# Schematic.net
KiCad netlist of a schematic drawn in EAGLE
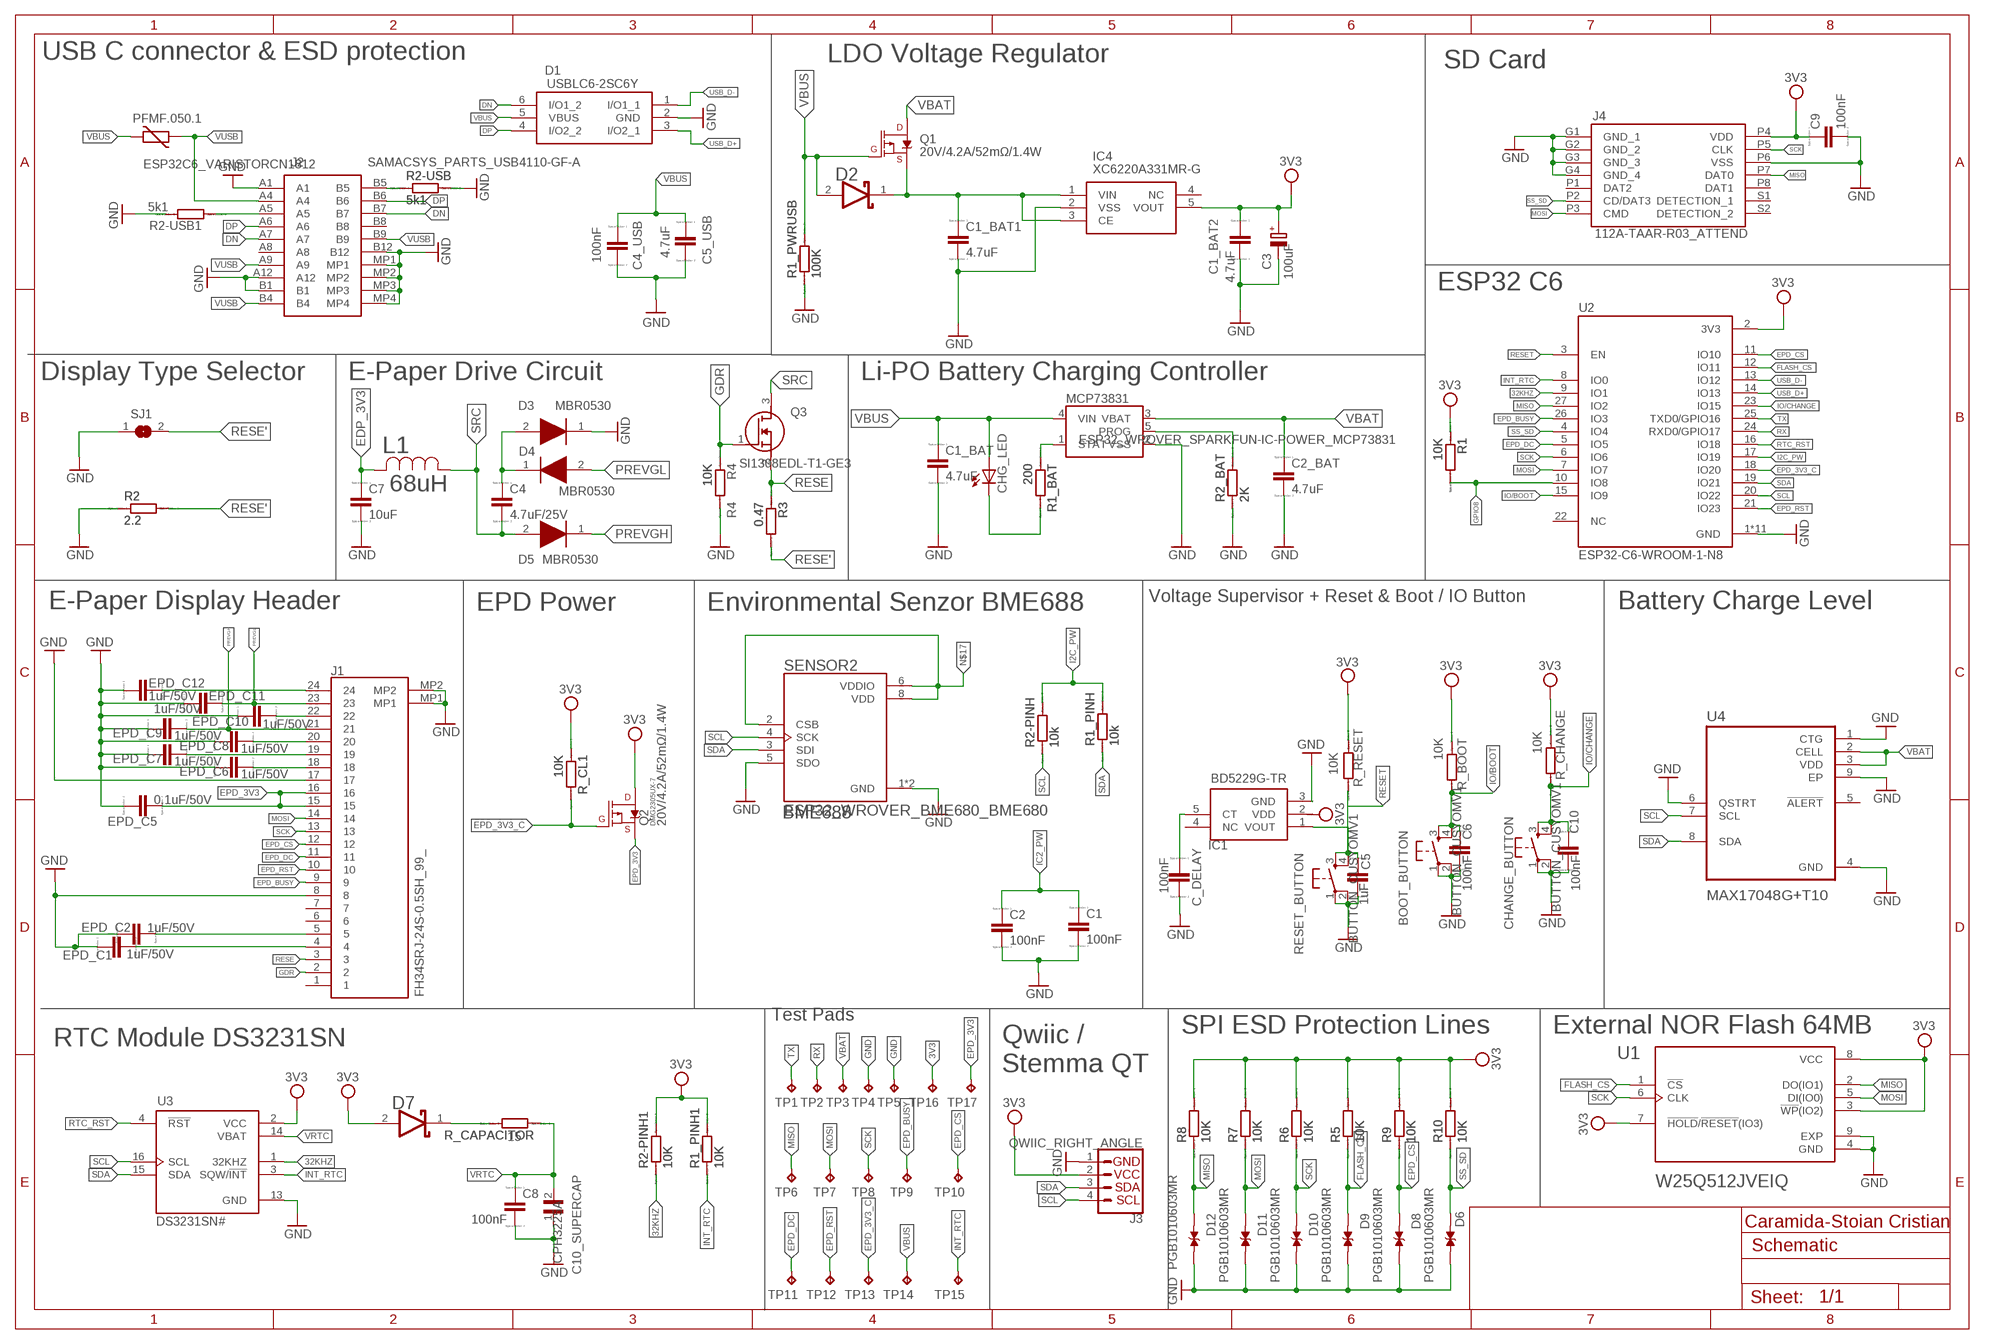
[diagram p0: schematic, sheet 1]

(export (version "E")
  (design (tool "Eeschema 10.0.6"))
  (components
    (comp (ref "BOOT_BUTTON")
      (value "BUTTON_CUSYOMV1")
      (footprint "eagle-import:MYBUTTON")
      (libsource (lib "eagle-import") (part "BUTTON_CUSYOMV1"))
    )
    (comp (ref "C1")
      (value "100nF")
      (footprint "eagle-import:ESP32_WROVER_EAGLE-LTSPICE_C0402")
      (libsource (lib "eagle-import") (part "ESP32_WROVER_EAGLE-LTSPICE_CC0402"))
    )
    (comp (ref "C1_BAT")
      (value "4.7uF")
      (footprint "eagle-import:ESP32_WROVER_EAGLE-LTSPICE_C0402")
      (libsource (lib "eagle-import") (part "ESP32_WROVER_EAGLE-LTSPICE_CC0402"))
    )
    (comp (ref "C1_BAT1")
      (value "4.7uF")
      (footprint "eagle-import:ESP32_WROVER_EAGLE-LTSPICE_C0402")
      (libsource (lib "eagle-import") (part "ESP32_WROVER_EAGLE-LTSPICE_CC0402"))
    )
    (comp (ref "C1_BAT2")
      (value "4.7uF")
      (footprint "eagle-import:ESP32_WROVER_EAGLE-LTSPICE_C0402")
      (libsource (lib "eagle-import") (part "ESP32_WROVER_EAGLE-LTSPICE_CC0402"))
    )
    (comp (ref "C2")
      (value "100nF")
      (footprint "eagle-import:ESP32_WROVER_EAGLE-LTSPICE_C0402")
      (libsource (lib "eagle-import") (part "ESP32_WROVER_EAGLE-LTSPICE_CC0402"))
    )
    (comp (ref "C2_BAT")
      (value "4.7uF")
      (footprint "eagle-import:ESP32_WROVER_EAGLE-LTSPICE_C0402")
      (libsource (lib "eagle-import") (part "ESP32_WROVER_EAGLE-LTSPICE_CC0402"))
    )
    (comp (ref "C3")
      (value "100uF")
      (footprint "eagle-import:RCL_CT3528")
      (libsource (lib "eagle-import") (part "RCL_CPOL-EUCT3528"))
    )
    (comp (ref "C4")
      (value "4.7uF/25V")
      (footprint "eagle-import:ESP32_WROVER_EAGLE-LTSPICE_C0402")
      (libsource (lib "eagle-import") (part "ESP32_WROVER_EAGLE-LTSPICE_CC0402"))
    )
    (comp (ref "C4_USB")
      (value "100nF")
      (footprint "eagle-import:ESP32_WROVER_EAGLE-LTSPICE_C0402")
      (libsource (lib "eagle-import") (part "ESP32_WROVER_EAGLE-LTSPICE_CC0402"))
    )
    (comp (ref "C5")
      (value "1uF")
      (footprint "eagle-import:ESP32_WROVER_EAGLE-LTSPICE_C0402")
      (libsource (lib "eagle-import") (part "EAGLE-LTSPICE_CC0402"))
    )
    (comp (ref "C5_USB")
      (value "4.7uF")
      (footprint "eagle-import:ESP32_WROVER_EAGLE-LTSPICE_C0402")
      (libsource (lib "eagle-import") (part "ESP32_WROVER_EAGLE-LTSPICE_CC0402"))
    )
    (comp (ref "C6")
      (value "100nF")
      (footprint "eagle-import:ESP32_WROVER_EAGLE-LTSPICE_C0402")
      (libsource (lib "eagle-import") (part "EAGLE-LTSPICE_CC0402"))
    )
    (comp (ref "C7")
      (value "10uF")
      (footprint "eagle-import:ESP32_WROVER_EAGLE-LTSPICE_C0402")
      (libsource (lib "eagle-import") (part "ESP32_WROVER_EAGLE-LTSPICE_CC0402"))
    )
    (comp (ref "C8")
      (value "100nF")
      (footprint "eagle-import:ESP32_WROVER_EAGLE-LTSPICE_C0402")
      (libsource (lib "eagle-import") (part "ESP32_WROVER_EAGLE-LTSPICE_CC0402"))
    )
    (comp (ref "C9")
      (value "100nF")
      (footprint "eagle-import:ESP32_WROVER_EAGLE-LTSPICE_C0402")
      (libsource (lib "eagle-import") (part "ESP32_WROVER_EAGLE-LTSPICE_CC0402"))
    )
    (comp (ref "C10")
      (value "100nF")
      (footprint "eagle-import:ESP32_WROVER_EAGLE-LTSPICE_C0402")
      (libsource (lib "eagle-import") (part "EAGLE-LTSPICE_CC0402"))
    )
    (comp (ref "C10_SUPERCAP")
      (value "CPH3225A")
      (footprint "eagle-import:CAPCP3225X100N")
      (fields (field (name "MF") "Seiko Instruments"))
      (libsource (lib "eagle-import") (part "CPH3225A"))
    )
    (comp (ref "CHANGE_BUTTON")
      (value "BUTTON_CUSYOMV1")
      (footprint "eagle-import:MYBUTTON")
      (libsource (lib "eagle-import") (part "BUTTON_CUSYOMV1"))
    )
    (comp (ref "CHG_LED")
      (value "ADAFRUIT_LEDCHIP-LED0603")
      (footprint "eagle-import:ADAFRUIT_CHIP-LED0603")
      (libsource (lib "eagle-import") (part "ADAFRUIT_LEDCHIP-LED0603"))
    )
    (comp (ref "C_DELAY")
      (value "100nF")
      (footprint "eagle-import:ESP32_WROVER_EAGLE-LTSPICE_C0402")
      (libsource (lib "eagle-import") (part "ESP32_WROVER_EAGLE-LTSPICE_CC0402"))
    )
    (comp (ref "D1")
      (value "USBLC6-2SC6Y")
      (footprint "eagle-import:SOT95P280X145-6N")
      (fields (field (name "MF") "STMicroelectronics"))
      (libsource (lib "eagle-import") (part "USBLC6-2SC6Y"))
    )
    (comp (ref "D2")
      (value "ESP32_WROVER_AVX---SD0805S020S1R0_AVX_SD0805S020S1R0_0_0AVX_SD0805S020S1R0_0_0")
      (footprint "eagle-import:ESP32_WROVER_AVX---SD0805S020S1R0_AVX_SD0805S020S1R0_0")
      (fields
        (field (name "DIGIKEY_PART_NUMBER") "478-7800-1-ND")
        (field (name "MF") "AVX")
        (field (name "MOUSER_PART_NUMBER") "581-SD0805S020S1R0")
      )
      (libsource (lib "eagle-import") (part "ESP32_WROVER_AVX---SD0805S020S1R0_AVX_SD0805S020S1R0_0_0AVX_SD0805S020S1R0_0_0"))
    )
    (comp (ref "D3")
      (value "MBR0530")
      (footprint "eagle-import:SOD3716X135N")
      (fields (field (name "MF") "ON Semiconductor"))
      (libsource (lib "eagle-import") (part "MBR0530"))
    )
    (comp (ref "D4")
      (value "MBR0530")
      (footprint "eagle-import:SOD3716X135N")
      (fields (field (name "MF") "ON Semiconductor"))
      (libsource (lib "eagle-import") (part "MBR0530"))
    )
    (comp (ref "D5")
      (value "MBR0530")
      (footprint "eagle-import:SOD3716X135N")
      (fields (field (name "MF") "ON Semiconductor"))
      (libsource (lib "eagle-import") (part "MBR0530"))
    )
    (comp (ref "D6")
      (value "PGB1010603MR")
      (footprint "eagle-import:DIOC1608X36N")
      (fields (field (name "MF") "Littelfuse Inc."))
      (libsource (lib "eagle-import") (part "PGB1010603MR"))
    )
    (comp (ref "D7")
      (value "ESP32_WROVER_AVX---SD0805S020S1R0_AVX_SD0805S020S1R0_0_0AVX_SD0805S020S1R0_0_0")
      (footprint "eagle-import:ESP32_WROVER_AVX---SD0805S020S1R0_AVX_SD0805S020S1R0_0")
      (fields
        (field (name "DIGIKEY_PART_NUMBER") "478-7800-1-ND")
        (field (name "MF") "AVX")
        (field (name "MOUSER_PART_NUMBER") "581-SD0805S020S1R0")
      )
      (libsource (lib "eagle-import") (part "ESP32_WROVER_AVX---SD0805S020S1R0_AVX_SD0805S020S1R0_0_0AVX_SD0805S020S1R0_0_0"))
    )
    (comp (ref "D8")
      (value "PGB1010603MR")
      (footprint "eagle-import:DIOC1608X36N")
      (fields (field (name "MF") "Littelfuse Inc."))
      (libsource (lib "eagle-import") (part "PGB1010603MR"))
    )
    (comp (ref "D9")
      (value "PGB1010603MR")
      (footprint "eagle-import:DIOC1608X36N")
      (fields (field (name "MF") "Littelfuse Inc."))
      (libsource (lib "eagle-import") (part "PGB1010603MR"))
    )
    (comp (ref "D10")
      (value "PGB1010603MR")
      (footprint "eagle-import:DIOC1608X36N")
      (fields (field (name "MF") "Littelfuse Inc."))
      (libsource (lib "eagle-import") (part "PGB1010603MR"))
    )
    (comp (ref "D11")
      (value "PGB1010603MR")
      (footprint "eagle-import:DIOC1608X36N")
      (fields (field (name "MF") "Littelfuse Inc."))
      (libsource (lib "eagle-import") (part "PGB1010603MR"))
    )
    (comp (ref "D12")
      (value "PGB1010603MR")
      (footprint "eagle-import:DIOC1608X36N")
      (fields (field (name "MF") "Littelfuse Inc."))
      (libsource (lib "eagle-import") (part "PGB1010603MR"))
    )
    (comp (ref "EPD_C1")
      (value "1uF/50V")
      (footprint "eagle-import:ESP32_WROVER_EAGLE-LTSPICE_C0402")
      (libsource (lib "eagle-import") (part "EAGLE-LTSPICE_CC0402"))
    )
    (comp (ref "EPD_C2")
      (value "1uF/50V")
      (footprint "eagle-import:ESP32_WROVER_EAGLE-LTSPICE_C0402")
      (libsource (lib "eagle-import") (part "EAGLE-LTSPICE_CC0402"))
    )
    (comp (ref "EPD_C5")
      (value "0.1uF/50V")
      (footprint "eagle-import:ESP32_WROVER_EAGLE-LTSPICE_C0402")
      (libsource (lib "eagle-import") (part "EAGLE-LTSPICE_CC0402"))
    )
    (comp (ref "EPD_C6")
      (value "1uF/50V")
      (footprint "eagle-import:ESP32_WROVER_EAGLE-LTSPICE_C0402")
      (libsource (lib "eagle-import") (part "EAGLE-LTSPICE_CC0402"))
    )
    (comp (ref "EPD_C7")
      (value "1uF/50V")
      (footprint "eagle-import:ESP32_WROVER_EAGLE-LTSPICE_C0402")
      (libsource (lib "eagle-import") (part "EAGLE-LTSPICE_CC0402"))
    )
    (comp (ref "EPD_C8")
      (value "1uF/50V")
      (footprint "eagle-import:ESP32_WROVER_EAGLE-LTSPICE_C0402")
      (libsource (lib "eagle-import") (part "EAGLE-LTSPICE_CC0402"))
    )
    (comp (ref "EPD_C9")
      (value "1uF/50V")
      (footprint "eagle-import:ESP32_WROVER_EAGLE-LTSPICE_C0402")
      (libsource (lib "eagle-import") (part "EAGLE-LTSPICE_CC0402"))
    )
    (comp (ref "EPD_C10")
      (value "1uF/50V")
      (footprint "eagle-import:ESP32_WROVER_EAGLE-LTSPICE_C0402")
      (libsource (lib "eagle-import") (part "EAGLE-LTSPICE_CC0402"))
    )
    (comp (ref "EPD_C11")
      (value "1uF/50V")
      (footprint "eagle-import:ESP32_WROVER_EAGLE-LTSPICE_C0402")
      (libsource (lib "eagle-import") (part "EAGLE-LTSPICE_CC0402"))
    )
    (comp (ref "EPD_C12")
      (value "1uF/50V")
      (footprint "eagle-import:ESP32_WROVER_EAGLE-LTSPICE_C0402")
      (libsource (lib "eagle-import") (part "EAGLE-LTSPICE_CC0402"))
    )
    (comp (ref "IC1")
      (value "BD5229G-TR")
      (footprint "eagle-import:SOT95P280X125-5N")
      (fields (field (name "MOUSER_PART_NUMBER") "755-BD5229G-TR"))
      (libsource (lib "eagle-import") (part "BD5229G-TR"))
    )
    (comp (ref "IC4")
      (value "XC6220A331MR-G")
      (footprint "eagle-import:ESP32_WROVER_SPARKFUN-IC-POWER_SOT23-5")
      (fields (field (name "MOUSER_PART_NUMBER") "865-XC6220A331MR-G"))
      (libsource (lib "eagle-import") (part "XC6220A331MR-G"))
    )
    (comp (ref "J1")
      (value "FH34SRJ-24S-0.5SH_99_")
      (footprint "eagle-import:FH34SRJ24S05SH99")
      (fields
        (field (name "MANUFACTURER_PART_NUMBER") "FH34SRJ-24S-0.5SH(99)")
        (field (name "MOUSER_PART_NUMBER") "798-FH34SRJ24S05SH99")
      )
      (libsource (lib "eagle-import") (part "FH34SRJ-24S-0.5SH_99_"))
    )
    (comp (ref "J2")
      (value "SAMACSYS_PARTS_USB4110-GF-A")
      (footprint "eagle-import:SAMACSYS_PARTS_USB4110GFA")
      (fields
        (field (name "MANUFACTURER_PART_NUMBER") "USB4110-GF-A")
        (field (name "MOUSER_PART_NUMBER") "640-USB4110-GF-A")
      )
      (libsource (lib "eagle-import") (part "SAMACSYS_PARTS_USB4110-GF-A"))
    )
    (comp (ref "J3")
      (value "QWIIC_RIGHT_ANGLE")
      (footprint "eagle-import:JST04_1MM_RA")
      (libsource (lib "eagle-import") (part "QWIIC_CONNECTORJS-1MM"))
    )
    (comp (ref "J4")
      (value "112A-TAAR-R03_ATTEND")
      (footprint "eagle-import:112ATAARR03ATTEND")
      (fields (field (name "MANUFACTURER_PART_NUMBER") "112A-TAAR-R03 ATTEND"))
      (libsource (lib "eagle-import") (part "112A-TAAR-R03_ATTEND"))
    )
    (comp (ref "L1")
      (value "68uH")
      (footprint "eagle-import:IND_4828-WE-TPC_WRE")
      (fields
        (field (name "MANUFACTURER_PART_NUMBER") "744043680")
        (field (name "COPYRIGHT") "Copyright (C) 2024 Ultra Librarian. All rights reserved.")
      )
      (libsource (lib "eagle-import") (part "744043680IND_4828-WE-TPC_WRE"))
    )
    (comp (ref "MCP73831")
      (value "ESP32_WROVER_SPARKFUN-IC-POWER_MCP73831")
      (footprint "eagle-import:ESP32_WROVER_SPARKFUN-IC-POWER_SOT23-5")
      (libsource (lib "eagle-import") (part "ESP32_WROVER_SPARKFUN-IC-POWER_MCP73831"))
    )
    (comp (ref "PFMF.050.1")
      (value "ESP32C6_VARISTORCN1812")
      (footprint "eagle-import:ESP32C6_VARISTOR_CT_CN1812")
      (libsource (lib "eagle-import") (part "ESP32C6_VARISTORCN1812"))
    )
    (comp (ref "Q1")
      (value "20V/4.2A/52mΩ/1.4W")
      (footprint "eagle-import:ESP32_WROVER_SPARKFUN-DISCRETESEMI_SOT23-3")
      (libsource (lib "eagle-import") (part "ESP32_WROVER_SPARKFUN-DISCRETESEMI_MOSFET_PCH-DMG2305UX-7"))
    )
    (comp (ref "Q2")
      (value "20V/4.2A/52mΩ/1.4W")
      (footprint "eagle-import:ESP32_WROVER_SPARKFUN-DISCRETESEMI_SOT23-3")
      (libsource (lib "eagle-import") (part "ESP32_WROVER_SPARKFUN-DISCRETESEMI_MOSFET_PCH-DMG2305UX-7"))
    )
    (comp (ref "Q3")
      (value "SI1308EDL-T1-GE3")
      (footprint "eagle-import:SOT65P210X110-3N")
      (fields (field (name "MF") "Vishay Siliconix"))
      (libsource (lib "eagle-import") (part "SI1308EDL-T1-GE3"))
    )
    (comp (ref "R1")
      (value "10K")
      (footprint "eagle-import:ESP32_WROVER_EAGLE-LTSPICE_R0402")
      (libsource (lib "eagle-import") (part "ESP32_WROVER_EAGLE-LTSPICE_RR0402"))
    )
    (comp (ref "R1_BAT")
      (value "200")
      (footprint "eagle-import:ESP32_WROVER_EAGLE-LTSPICE_R0402")
      (libsource (lib "eagle-import") (part "ESP32_WROVER_EAGLE-LTSPICE_RR0402"))
    )
    (comp (ref "R1_PINH")
      (value "10k")
      (footprint "eagle-import:ESP32_WROVER_EAGLE-LTSPICE_R0402")
      (libsource (lib "eagle-import") (part "ESP32_WROVER_EAGLE-LTSPICE_RR0402"))
    )
    (comp (ref "R1_PINH1")
      (value "10K")
      (footprint "eagle-import:ESP32_WROVER_EAGLE-LTSPICE_R0402")
      (libsource (lib "eagle-import") (part "ESP32_WROVER_EAGLE-LTSPICE_RR0402"))
    )
    (comp (ref "R1_PWRUSB")
      (value "100K")
      (footprint "eagle-import:ESP32_WROVER_EAGLE-LTSPICE_R0402")
      (libsource (lib "eagle-import") (part "ESP32_WROVER_EAGLE-LTSPICE_RR0402"))
    )
    (comp (ref "R2")
      (value "2.2")
      (footprint "eagle-import:ESP32_WROVER_EAGLE-LTSPICE_R0402")
      (libsource (lib "eagle-import") (part "ESP32_WROVER_EAGLE-LTSPICE_RR0402"))
    )
    (comp (ref "R2-PINH")
      (value "10k")
      (footprint "eagle-import:ESP32_WROVER_EAGLE-LTSPICE_R0402")
      (libsource (lib "eagle-import") (part "ESP32_WROVER_EAGLE-LTSPICE_RR0402"))
    )
    (comp (ref "R2-PINH1")
      (value "10K")
      (footprint "eagle-import:ESP32_WROVER_EAGLE-LTSPICE_R0402")
      (libsource (lib "eagle-import") (part "ESP32_WROVER_EAGLE-LTSPICE_RR0402"))
    )
    (comp (ref "R2-USB")
      (value "5k1")
      (footprint "eagle-import:ESP32_WROVER_EAGLE-LTSPICE_R0402")
      (libsource (lib "eagle-import") (part "ESP32_WROVER_EAGLE-LTSPICE_RR0402"))
    )
    (comp (ref "R2-USB1")
      (value "5k1")
      (footprint "eagle-import:ESP32_WROVER_EAGLE-LTSPICE_R0402")
      (libsource (lib "eagle-import") (part "ESP32_WROVER_EAGLE-LTSPICE_RR0402"))
    )
    (comp (ref "R2_BAT")
      (value "2K")
      (footprint "eagle-import:ESP32_WROVER_EAGLE-LTSPICE_R0402")
      (libsource (lib "eagle-import") (part "ESP32_WROVER_EAGLE-LTSPICE_RR0402"))
    )
    (comp (ref "R3")
      (value "0.47")
      (footprint "eagle-import:ESP32_WROVER_EAGLE-LTSPICE_R0402")
      (libsource (lib "eagle-import") (part "ESP32_WROVER_EAGLE-LTSPICE_RR0402"))
    )
    (comp (ref "R4")
      (value "10K")
      (footprint "eagle-import:ESP32_WROVER_EAGLE-LTSPICE_R0402")
      (libsource (lib "eagle-import") (part "ESP32_WROVER_EAGLE-LTSPICE_RR0402"))
    )
    (comp (ref "R5")
      (value "10K")
      (footprint "eagle-import:ESP32_WROVER_EAGLE-LTSPICE_R0402")
      (libsource (lib "eagle-import") (part "ESP32_WROVER_EAGLE-LTSPICE_RR0402"))
    )
    (comp (ref "R6")
      (value "10K")
      (footprint "eagle-import:ESP32_WROVER_EAGLE-LTSPICE_R0402")
      (libsource (lib "eagle-import") (part "ESP32_WROVER_EAGLE-LTSPICE_RR0402"))
    )
    (comp (ref "R7")
      (value "10K")
      (footprint "eagle-import:ESP32_WROVER_EAGLE-LTSPICE_R0402")
      (libsource (lib "eagle-import") (part "ESP32_WROVER_EAGLE-LTSPICE_RR0402"))
    )
    (comp (ref "R8")
      (value "10K")
      (footprint "eagle-import:ESP32_WROVER_EAGLE-LTSPICE_R0402")
      (libsource (lib "eagle-import") (part "ESP32_WROVER_EAGLE-LTSPICE_RR0402"))
    )
    (comp (ref "R9")
      (value "10K")
      (footprint "eagle-import:ESP32_WROVER_EAGLE-LTSPICE_R0402")
      (libsource (lib "eagle-import") (part "ESP32_WROVER_EAGLE-LTSPICE_RR0402"))
    )
    (comp (ref "R10")
      (value "10K")
      (footprint "eagle-import:ESP32_WROVER_EAGLE-LTSPICE_R0402")
      (libsource (lib "eagle-import") (part "ESP32_WROVER_EAGLE-LTSPICE_RR0402"))
    )
    (comp (ref "RESET_BUTTON")
      (value "BUTTON_CUSYOMV1")
      (footprint "eagle-import:MYBUTTON")
      (libsource (lib "eagle-import") (part "BUTTON_CUSYOMV1"))
    )
    (comp (ref "R_BOOT")
      (value "10K")
      (footprint "eagle-import:ESP32_WROVER_EAGLE-LTSPICE_R0402")
      (libsource (lib "eagle-import") (part "ESP32_WROVER_EAGLE-LTSPICE_RR0402"))
    )
    (comp (ref "R_CAPACITOR")
      (value "15")
      (footprint "eagle-import:ESP32_WROVER_EAGLE-LTSPICE_R0402")
      (libsource (lib "eagle-import") (part "ESP32_WROVER_EAGLE-LTSPICE_RR0402"))
    )
    (comp (ref "R_CHANGE")
      (value "10K")
      (footprint "eagle-import:ESP32_WROVER_EAGLE-LTSPICE_R0402")
      (libsource (lib "eagle-import") (part "ESP32_WROVER_EAGLE-LTSPICE_RR0402"))
    )
    (comp (ref "R_CL1")
      (value "10K")
      (footprint "eagle-import:ESP32_WROVER_EAGLE-LTSPICE_R0402")
      (libsource (lib "eagle-import") (part "ESP32_WROVER_EAGLE-LTSPICE_RR0402"))
    )
    (comp (ref "R_RESET")
      (value "10K")
      (footprint "eagle-import:ESP32_WROVER_EAGLE-LTSPICE_R0402")
      (libsource (lib "eagle-import") (part "ESP32_WROVER_EAGLE-LTSPICE_RR0402"))
    )
    (comp (ref "SENSOR2")
      (value "ESP32_WROVER_BME680_BME680")
      (footprint "eagle-import:ESP32_WROVER_BME680_PSON80P300X300X100-8N")
      (fields (field (name "MF") "Bosch Sensortec") (field (name "MP") "BME680"))
      (libsource (lib "eagle-import") (part "ESP32_WROVER_BME680_BME680"))
    )
    (comp (ref "SJ1")
      (value "SJ")
      (footprint "eagle-import:SOT65P210X110-3N")
      (libsource (lib "eagle-import") (part "SJ"))
    )
    (comp (ref "TP1")
      (value "TPTP20R")
      (footprint "eagle-import:TP20R")
      (libsource (lib "eagle-import") (part "TPTP20R"))
    )
    (comp (ref "TP2")
      (value "TPTP20R")
      (footprint "eagle-import:TP20R")
      (libsource (lib "eagle-import") (part "TPTP20R"))
    )
    (comp (ref "TP3")
      (value "TPTP20R")
      (footprint "eagle-import:TP20R")
      (libsource (lib "eagle-import") (part "TPTP20R"))
    )
    (comp (ref "TP4")
      (value "TPTP20R")
      (footprint "eagle-import:TP20R")
      (libsource (lib "eagle-import") (part "TPTP20R"))
    )
    (comp (ref "TP5")
      (value "TPTP20R")
      (footprint "eagle-import:TP20R")
      (libsource (lib "eagle-import") (part "TPTP20R"))
    )
    (comp (ref "TP6")
      (value "TPTP20R")
      (footprint "eagle-import:TP20R")
      (libsource (lib "eagle-import") (part "TPTP20R"))
    )
    (comp (ref "TP7")
      (value "TPTP20R")
      (footprint "eagle-import:TP20R")
      (libsource (lib "eagle-import") (part "TPTP20R"))
    )
    (comp (ref "TP8")
      (value "TPTP20R")
      (footprint "eagle-import:TP20R")
      (libsource (lib "eagle-import") (part "TPTP20R"))
    )
    (comp (ref "TP9")
      (value "TPTP20R")
      (footprint "eagle-import:TP20R")
      (libsource (lib "eagle-import") (part "TPTP20R"))
    )
    (comp (ref "TP10")
      (value "TPTP20R")
      (footprint "eagle-import:TP20R")
      (libsource (lib "eagle-import") (part "TPTP20R"))
    )
    (comp (ref "TP11")
      (value "TPTP20R")
      (footprint "eagle-import:TP20R")
      (libsource (lib "eagle-import") (part "TPTP20R"))
    )
    (comp (ref "TP12")
      (value "TPTP20R")
      (footprint "eagle-import:TP20R")
      (libsource (lib "eagle-import") (part "TPTP20R"))
    )
    (comp (ref "TP13")
      (value "TPTP20R")
      (footprint "eagle-import:TP20R")
      (libsource (lib "eagle-import") (part "TPTP20R"))
    )
    (comp (ref "TP14")
      (value "TPTP20R")
      (footprint "eagle-import:TP20R")
      (libsource (lib "eagle-import") (part "TPTP20R"))
    )
    (comp (ref "TP15")
      (value "TPTP20R")
      (footprint "eagle-import:TP20R")
      (libsource (lib "eagle-import") (part "TPTP20R"))
    )
    (comp (ref "TP16")
      (value "TPTP20R")
      (footprint "eagle-import:TP20R")
      (libsource (lib "eagle-import") (part "TPTP20R"))
    )
    (comp (ref "TP17")
      (value "TPTP20R")
      (footprint "eagle-import:TP20R")
      (libsource (lib "eagle-import") (part "TPTP20R"))
    )
    (comp (ref "U1")
      (value "W25Q512JVEIQ")
      (footprint "eagle-import:SON127P600X800X80-9N")
      (fields (field (name "MF") "Winbond Electronics"))
      (libsource (lib "eagle-import") (part "W25Q512JVEIQ"))
    )
    (comp (ref "U2")
      (value "ESP32-C6-WROOM-1-N8")
      (footprint "eagle-import:XCVR_ESP32-C6-WROOM-1-N8")
      (fields (field (name "MF") "Espressif Systems"))
      (libsource (lib "eagle-import") (part "ESP32-C6-WROOM-1-N8"))
    )
    (comp (ref "U3")
      (value "DS3231SN#")
      (footprint "eagle-import:SOIC127P1032X265-16N")
      (fields (field (name "MF") "Analog Devices"))
      (libsource (lib "eagle-import") (part "DS3231SN#"))
    )
    (comp (ref "U4")
      (value "MAX17048G+T10")
      (footprint "eagle-import:SON50P200X200X80-9N")
      (fields (field (name "MF") "Analog Devices"))
      (libsource (lib "eagle-import") (part "MAX17048G+T10"))
    )
  )
  (nets
    (net (code "1") (name "3V3") (class "Default")
      (node (ref "C1_BAT2") (pin "1") (pinfunction "1_1") (pintype "passive"))
      (node (ref "C3") (pin "+") (pinfunction "+_+") (pintype "passive"))
      (node (ref "C9") (pin "1") (pinfunction "1_1") (pintype "passive"))
      (node (ref "D7") (pin "2") (pinfunction "ANODE_2") (pintype "bidirectional"))
      (node (ref "IC4") (pin "5") (pinfunction "VOUT_5") (pintype "bidirectional"))
      (node (ref "J3") (pin "2") (pinfunction "2_2") (pintype "power_in"))
      (node (ref "J4") (pin "P4") (pinfunction "VDD_P4") (pintype "bidirectional"))
      (node (ref "Q2") (pin "3") (pinfunction "D_3") (pintype "bidirectional"))
      (node (ref "R1") (pin "1") (pinfunction "1_1") (pintype "passive"))
      (node (ref "R10") (pin "2") (pinfunction "2_2") (pintype "passive"))
      (node (ref "R1_PINH1") (pin "2") (pinfunction "2_2") (pintype "passive"))
      (node (ref "R2-PINH1") (pin "2") (pinfunction "2_2") (pintype "passive"))
      (node (ref "R5") (pin "2") (pinfunction "2_2") (pintype "passive"))
      (node (ref "R6") (pin "2") (pinfunction "2_2") (pintype "passive"))
      (node (ref "R7") (pin "2") (pinfunction "2_2") (pintype "passive"))
      (node (ref "R8") (pin "2") (pinfunction "2_2") (pintype "passive"))
      (node (ref "R9") (pin "2") (pinfunction "2_2") (pintype "passive"))
      (node (ref "R_BOOT") (pin "2") (pinfunction "2_2") (pintype "passive"))
      (node (ref "R_CHANGE") (pin "2") (pinfunction "2_2") (pintype "passive"))
      (node (ref "R_CL1") (pin "1") (pinfunction "1_1") (pintype "passive"))
      (node (ref "R_RESET") (pin "2") (pinfunction "2_2") (pintype "passive"))
      (node (ref "TP16") (pin "TP") (pinfunction "TP_TP") (pintype "input"))
      (node (ref "U1") (pin "3") (pinfunction "~{WP}(IO2)_3") (pintype "bidirectional"))
      (node (ref "U1") (pin "7") (pinfunction "~{HOLD}/~{RESET}(IO3)_7") (pintype "bidirectional"))
      (node (ref "U1") (pin "8") (pinfunction "VCC_8") (pintype "power_in"))
      (node (ref "U2") (pin "2") (pinfunction "3V3_2") (pintype "power_in"))
      (node (ref "U3") (pin "2") (pinfunction "VCC_2") (pintype "power_in"))
    )
    (net (code "2") (name "32KHZ") (class "Default")
      (node (ref "R2-PINH1") (pin "1") (pinfunction "1_1") (pintype "passive"))
      (node (ref "U2") (pin "9") (pinfunction "IO1_9") (pintype "bidirectional"))
      (node (ref "U3") (pin "1") (pinfunction "32KHZ_1") (pintype "output"))
    )
    (net (code "3") (name "DN") (class "Default")
      (node (ref "D1") (pin "6") (pinfunction "I/O1_2_6") (pintype "bidirectional"))
      (node (ref "J2") (pin "A7") (pinfunction "A7_A7") (pintype "bidirectional"))
      (node (ref "J2") (pin "B7") (pinfunction "B7_B7") (pintype "bidirectional"))
    )
    (net (code "4") (name "DP") (class "Default")
      (node (ref "D1") (pin "4") (pinfunction "I/O2_2_4") (pintype "bidirectional"))
      (node (ref "J2") (pin "A6") (pinfunction "A6_A6") (pintype "bidirectional"))
      (node (ref "J2") (pin "B6") (pinfunction "B6_B6") (pintype "bidirectional"))
    )
    (net (code "5") (name "EDP_3V3") (class "Default")
      (node (ref "C7") (pin "1") (pinfunction "1_1") (pintype "passive"))
      (node (ref "L1") (pin "2") (pinfunction "2_2") (pintype "passive"))
    )
    (net (code "6") (name "EPD_3V3") (class "Default")
      (node (ref "EPD_C5") (pin "2") (pinfunction "2_2") (pintype "passive"))
      (node (ref "J1") (pin "15") (pinfunction "15_15") (pintype "bidirectional"))
      (node (ref "J1") (pin "16") (pinfunction "16_16") (pintype "bidirectional"))
      (node (ref "Q2") (pin "2") (pinfunction "S_2") (pintype "bidirectional"))
      (node (ref "TP17") (pin "TP") (pinfunction "TP_TP") (pintype "input"))
    )
    (net (code "7") (name "EPD_3V3_C") (class "Default")
      (node (ref "Q2") (pin "1") (pinfunction "G_1") (pintype "bidirectional"))
      (node (ref "R_CL1") (pin "2") (pinfunction "2_2") (pintype "passive"))
      (node (ref "TP13") (pin "TP") (pinfunction "TP_TP") (pintype "input"))
      (node (ref "U2") (pin "18") (pinfunction "IO20_18") (pintype "bidirectional"))
    )
    (net (code "8") (name "EPD_BUSY") (class "Default")
      (node (ref "J1") (pin "9") (pinfunction "9_9") (pintype "bidirectional"))
      (node (ref "TP9") (pin "TP") (pinfunction "TP_TP") (pintype "input"))
      (node (ref "U2") (pin "26") (pinfunction "IO3_26") (pintype "bidirectional"))
    )
    (net (code "9") (name "EPD_CS") (class "Default")
      (node (ref "D8") (pin "1") (pinfunction "1_1") (pintype "passive"))
      (node (ref "J1") (pin "12") (pinfunction "12_12") (pintype "bidirectional"))
      (node (ref "R9") (pin "1") (pinfunction "1_1") (pintype "passive"))
      (node (ref "TP10") (pin "TP") (pinfunction "TP_TP") (pintype "input"))
      (node (ref "U2") (pin "11") (pinfunction "IO10_11") (pintype "bidirectional"))
    )
    (net (code "10") (name "EPD_DC") (class "Default")
      (node (ref "J1") (pin "11") (pinfunction "11_11") (pintype "bidirectional"))
      (node (ref "TP11") (pin "TP") (pinfunction "TP_TP") (pintype "input"))
      (node (ref "U2") (pin "5") (pinfunction "IO5_5") (pintype "bidirectional"))
    )
    (net (code "11") (name "EPD_RST") (class "Default")
      (node (ref "J1") (pin "10") (pinfunction "10_10") (pintype "bidirectional"))
      (node (ref "TP12") (pin "TP") (pinfunction "TP_TP") (pintype "input"))
      (node (ref "U2") (pin "21") (pinfunction "IO23_21") (pintype "bidirectional"))
    )
    (net (code "12") (name "FLASH_CS") (class "Default")
      (node (ref "D9") (pin "1") (pinfunction "1_1") (pintype "passive"))
      (node (ref "R5") (pin "1") (pinfunction "1_1") (pintype "passive"))
      (node (ref "U1") (pin "1") (pinfunction "~{CS}_1") (pintype "input"))
      (node (ref "U2") (pin "12") (pinfunction "IO11_12") (pintype "bidirectional"))
    )
    (net (code "13") (name "GDR") (class "Default")
      (node (ref "J1") (pin "2") (pinfunction "2_2") (pintype "bidirectional"))
      (node (ref "Q3") (pin "1") (pinfunction "G_1") (pintype "bidirectional"))
      (node (ref "R4") (pin "1") (pinfunction "1_1") (pintype "passive"))
    )
    (net (code "14") (name "GND") (class "Default")
      (node (ref "BOOT_BUTTON") (pin "1") (pinfunction "1_1") (pintype "passive"))
      (node (ref "BOOT_BUTTON") (pin "2") (pinfunction "2_2") (pintype "passive"))
      (node (ref "C1") (pin "2") (pinfunction "2_2") (pintype "passive"))
      (node (ref "C10") (pin "2") (pinfunction "2_2") (pintype "passive"))
      (node (ref "C10_SUPERCAP") (pin "1") (pinfunction "1_1") (pintype "passive"))
      (node (ref "C1_BAT") (pin "2") (pinfunction "2_2") (pintype "passive"))
      (node (ref "C1_BAT1") (pin "2") (pinfunction "2_2") (pintype "passive"))
      (node (ref "C1_BAT2") (pin "2") (pinfunction "2_2") (pintype "passive"))
      (node (ref "C2") (pin "2") (pinfunction "2_2") (pintype "passive"))
      (node (ref "C2_BAT") (pin "2") (pinfunction "2_2") (pintype "passive"))
      (node (ref "C3") (pin "-") (pinfunction "-_-") (pintype "passive"))
      (node (ref "C4_USB") (pin "2") (pinfunction "2_2") (pintype "passive"))
      (node (ref "C5") (pin "2") (pinfunction "2_2") (pintype "passive"))
      (node (ref "C5_USB") (pin "2") (pinfunction "2_2") (pintype "passive"))
      (node (ref "C6") (pin "2") (pinfunction "2_2") (pintype "passive"))
      (node (ref "C7") (pin "2") (pinfunction "2_2") (pintype "passive"))
      (node (ref "C8") (pin "2") (pinfunction "2_2") (pintype "passive"))
      (node (ref "C9") (pin "2") (pinfunction "2_2") (pintype "passive"))
      (node (ref "CHANGE_BUTTON") (pin "1") (pinfunction "1_1") (pintype "passive"))
      (node (ref "CHANGE_BUTTON") (pin "2") (pinfunction "2_2") (pintype "passive"))
      (node (ref "C_DELAY") (pin "2") (pinfunction "2_2") (pintype "passive"))
      (node (ref "D1") (pin "2") (pinfunction "GND_2") (pintype "bidirectional"))
      (node (ref "D10") (pin "2") (pinfunction "2_2") (pintype "passive"))
      (node (ref "D11") (pin "2") (pinfunction "2_2") (pintype "passive"))
      (node (ref "D12") (pin "2") (pinfunction "2_2") (pintype "passive"))
      (node (ref "D3") (pin "1") (pinfunction "K_1") (pintype "bidirectional"))
      (node (ref "D6") (pin "2") (pinfunction "2_2") (pintype "passive"))
      (node (ref "D8") (pin "2") (pinfunction "2_2") (pintype "passive"))
      (node (ref "D9") (pin "2") (pinfunction "2_2") (pintype "passive"))
      (node (ref "EPD_C1") (pin "1") (pinfunction "1_1") (pintype "passive"))
      (node (ref "EPD_C10") (pin "1") (pinfunction "1_1") (pintype "passive"))
      (node (ref "EPD_C11") (pin "1") (pinfunction "1_1") (pintype "passive"))
      (node (ref "EPD_C12") (pin "1") (pinfunction "1_1") (pintype "passive"))
      (node (ref "EPD_C2") (pin "1") (pinfunction "1_1") (pintype "passive"))
      (node (ref "EPD_C5") (pin "1") (pinfunction "1_1") (pintype "passive"))
      (node (ref "EPD_C6") (pin "1") (pinfunction "1_1") (pintype "passive"))
      (node (ref "EPD_C7") (pin "1") (pinfunction "1_1") (pintype "passive"))
      (node (ref "EPD_C8") (pin "1") (pinfunction "1_1") (pintype "passive"))
      (node (ref "EPD_C9") (pin "1") (pinfunction "1_1") (pintype "passive"))
      (node (ref "IC1") (pin "3") (pinfunction "GND_3") (pintype "bidirectional"))
      (node (ref "IC4") (pin "2") (pinfunction "VSS_2") (pintype "bidirectional"))
      (node (ref "J1") (pin "17") (pinfunction "17_17") (pintype "bidirectional"))
      (node (ref "J1") (pin "8") (pinfunction "8_8") (pintype "bidirectional"))
      (node (ref "J1") (pin "MP1") (pinfunction "MP1_MP1") (pintype "bidirectional"))
      (node (ref "J1") (pin "MP2") (pinfunction "MP2_MP2") (pintype "bidirectional"))
      (node (ref "J2") (pin "A1") (pinfunction "A1_A1") (pintype "bidirectional"))
      (node (ref "J2") (pin "A12") (pinfunction "A12_A12") (pintype "bidirectional"))
      (node (ref "J2") (pin "B1") (pinfunction "B1_B1") (pintype "bidirectional"))
      (node (ref "J2") (pin "B12") (pinfunction "B12_B12") (pintype "bidirectional"))
      (node (ref "J2") (pin "MP1") (pinfunction "MP1_MP1") (pintype "bidirectional"))
      (node (ref "J2") (pin "MP2") (pinfunction "MP2_MP2") (pintype "bidirectional"))
      (node (ref "J2") (pin "MP3") (pinfunction "MP3_MP3") (pintype "bidirectional"))
      (node (ref "J2") (pin "MP4") (pinfunction "MP4_MP4") (pintype "bidirectional"))
      (node (ref "J3") (pin "1") (pinfunction "1_1") (pintype "power_in"))
      (node (ref "J4") (pin "G1") (pinfunction "GND_1_G1") (pintype "bidirectional"))
      (node (ref "J4") (pin "G2") (pinfunction "GND_2_G2") (pintype "bidirectional"))
      (node (ref "J4") (pin "G3") (pinfunction "GND_3_G3") (pintype "bidirectional"))
      (node (ref "J4") (pin "G4") (pinfunction "GND_4_G4") (pintype "bidirectional"))
      (node (ref "J4") (pin "P6") (pinfunction "VSS_P6") (pintype "bidirectional"))
      (node (ref "MCP73831") (pin "2") (pinfunction "VSS_2") (pintype "power_in"))
      (node (ref "R1_PWRUSB") (pin "1") (pinfunction "1_1") (pintype "passive"))
      (node (ref "R2") (pin "1") (pinfunction "1_1") (pintype "passive"))
      (node (ref "R2-USB") (pin "2") (pinfunction "2_2") (pintype "passive"))
      (node (ref "R2-USB1") (pin "1") (pinfunction "1_1") (pintype "passive"))
      (node (ref "R2_BAT") (pin "1") (pinfunction "1_1") (pintype "passive"))
      (node (ref "R4") (pin "2") (pinfunction "2_2") (pintype "passive"))
      (node (ref "RESET_BUTTON") (pin "1") (pinfunction "1_1") (pintype "passive"))
      (node (ref "RESET_BUTTON") (pin "2") (pinfunction "2_2") (pintype "passive"))
      (node (ref "SENSOR2") (pin "1") (pinfunction "GND_1") (pintype "power_in"))
      (node (ref "SENSOR2") (pin "5") (pinfunction "SDO_5") (pintype "bidirectional"))
      (node (ref "SENSOR2") (pin "7") (pinfunction "GND_7") (pintype "power_in"))
      (node (ref "SJ1") (pin "1") (pinfunction "1_1") (pintype "passive"))
      (node (ref "TP4") (pin "TP") (pinfunction "TP_TP") (pintype "input"))
      (node (ref "TP5") (pin "TP") (pinfunction "TP_TP") (pintype "input"))
      (node (ref "U1") (pin "4") (pinfunction "GND_4") (pintype "power_in"))
      (node (ref "U1") (pin "9") (pinfunction "EXP_9") (pintype "passive"))
      (node (ref "U2") (pin "1") (pinfunction "GND_1") (pintype "power_in"))
      (node (ref "U2") (pin "28") (pinfunction "GND_28") (pintype "power_in"))
      (node (ref "U2") (pin "29_1") (pinfunction "GND_29_1") (pintype "power_in"))
      (node (ref "U2") (pin "29_2") (pinfunction "GND_29_2") (pintype "power_in"))
      (node (ref "U2") (pin "29_3") (pinfunction "GND_29_3") (pintype "power_in"))
      (node (ref "U2") (pin "29_4") (pinfunction "GND_29_4") (pintype "power_in"))
      (node (ref "U2") (pin "29_5") (pinfunction "GND_29_5") (pintype "power_in"))
      (node (ref "U2") (pin "29_6") (pinfunction "GND_29_6") (pintype "power_in"))
      (node (ref "U2") (pin "29_7") (pinfunction "GND_29_7") (pintype "power_in"))
      (node (ref "U2") (pin "29_8") (pinfunction "GND_29_8") (pintype "power_in"))
      (node (ref "U2") (pin "29_9") (pinfunction "GND_29_9") (pintype "power_in"))
      (node (ref "U3") (pin "13") (pinfunction "GND_13") (pintype "power_in"))
      (node (ref "U4") (pin "1") (pinfunction "CTG_1") (pintype "power_in"))
      (node (ref "U4") (pin "4") (pinfunction "GND_4") (pintype "power_in"))
      (node (ref "U4") (pin "6") (pinfunction "QSTRT_6") (pintype "input"))
      (node (ref "U4") (pin "9") (pinfunction "EP_9") (pintype "power_in"))
    )
    (net (code "15") (name "GPIO8") (class "Default")
      (node (ref "R1") (pin "2") (pinfunction "2_2") (pintype "passive"))
      (node (ref "U2") (pin "10") (pinfunction "IO8_10") (pintype "bidirectional"))
    )
    (net (code "16") (name "I2C_PW") (class "Default")
      (node (ref "R1_PINH") (pin "2") (pinfunction "2_2") (pintype "passive"))
      (node (ref "R2-PINH") (pin "2") (pinfunction "2_2") (pintype "passive"))
      (node (ref "U2") (pin "17") (pinfunction "IO19_17") (pintype "bidirectional"))
    )
    (net (code "17") (name "IC2_PW") (class "Default")
      (node (ref "C1") (pin "1") (pinfunction "1_1") (pintype "passive"))
      (node (ref "C2") (pin "1") (pinfunction "1_1") (pintype "passive"))
    )
    (net (code "18") (name "INT_RTC") (class "Default")
      (node (ref "R1_PINH1") (pin "1") (pinfunction "1_1") (pintype "passive"))
      (node (ref "TP15") (pin "TP") (pinfunction "TP_TP") (pintype "input"))
      (node (ref "U2") (pin "8") (pinfunction "IO0_8") (pintype "bidirectional"))
      (node (ref "U3") (pin "3") (pinfunction "SQW/~{INT}_3") (pintype "output"))
    )
    (net (code "19") (name "IO{slash}BOOT") (class "Default")
      (node (ref "BOOT_BUTTON") (pin "3") (pinfunction "3_3") (pintype "passive"))
      (node (ref "BOOT_BUTTON") (pin "4") (pinfunction "4_4") (pintype "passive"))
      (node (ref "C6") (pin "1") (pinfunction "1_1") (pintype "passive"))
      (node (ref "R_BOOT") (pin "1") (pinfunction "1_1") (pintype "passive"))
      (node (ref "U2") (pin "15") (pinfunction "IO9_15") (pintype "bidirectional"))
    )
    (net (code "20") (name "IO{slash}CHANGE") (class "Default")
      (node (ref "C10") (pin "1") (pinfunction "1_1") (pintype "passive"))
      (node (ref "CHANGE_BUTTON") (pin "3") (pinfunction "3_3") (pintype "passive"))
      (node (ref "CHANGE_BUTTON") (pin "4") (pinfunction "4_4") (pintype "passive"))
      (node (ref "R_CHANGE") (pin "1") (pinfunction "1_1") (pintype "passive"))
      (node (ref "U2") (pin "23") (pinfunction "IO15_23") (pintype "bidirectional"))
    )
    (net (code "21") (name "MISO") (class "Default")
      (node (ref "D12") (pin "1") (pinfunction "1_1") (pintype "passive"))
      (node (ref "J4") (pin "P7") (pinfunction "DAT0_P7") (pintype "bidirectional"))
      (node (ref "R8") (pin "1") (pinfunction "1_1") (pintype "passive"))
      (node (ref "TP6") (pin "TP") (pinfunction "TP_TP") (pintype "input"))
      (node (ref "U1") (pin "2") (pinfunction "DO(IO1)_2") (pintype "bidirectional"))
      (node (ref "U2") (pin "27") (pinfunction "IO2_27") (pintype "bidirectional"))
    )
    (net (code "22") (name "MOSI") (class "Default")
      (node (ref "D11") (pin "1") (pinfunction "1_1") (pintype "passive"))
      (node (ref "J1") (pin "14") (pinfunction "14_14") (pintype "bidirectional"))
      (node (ref "J4") (pin "P3") (pinfunction "CMD_P3") (pintype "bidirectional"))
      (node (ref "R7") (pin "1") (pinfunction "1_1") (pintype "passive"))
      (node (ref "TP7") (pin "TP") (pinfunction "TP_TP") (pintype "input"))
      (node (ref "U1") (pin "5") (pinfunction "DI(IO0)_5") (pintype "bidirectional"))
      (node (ref "U2") (pin "7") (pinfunction "IO7_7") (pintype "bidirectional"))
    )
    (net (code "23") (name "N$17") (class "Default")
      (node (ref "SENSOR2") (pin "2") (pinfunction "CSB_2") (pintype "input"))
      (node (ref "SENSOR2") (pin "6") (pinfunction "VDDIO_6") (pintype "power_in"))
      (node (ref "SENSOR2") (pin "8") (pinfunction "VDD_8") (pintype "power_in"))
    )
    (net (code "24") (name "Net-(CHG_LED-PadC)") (class "Default")
      (node (ref "CHG_LED") (pin "C") (pinfunction "C_C") (pintype "passive"))
      (node (ref "R1_BAT") (pin "2") (pinfunction "2_2") (pintype "passive"))
    )
    (net (code "25") (name "Net-(D2-CATHODE)") (class "Default")
      (node (ref "C1_BAT1") (pin "1") (pinfunction "1_1") (pintype "passive"))
      (node (ref "D2") (pin "1") (pinfunction "CATHODE_1") (pintype "bidirectional"))
      (node (ref "IC4") (pin "1") (pinfunction "VIN_1") (pintype "bidirectional"))
      (node (ref "IC4") (pin "3") (pinfunction "CE_3") (pintype "bidirectional"))
      (node (ref "Q1") (pin "2") (pinfunction "S_2") (pintype "bidirectional"))
    )
    (net (code "26") (name "Net-(D3-A)") (class "Default")
      (node (ref "C4") (pin "1") (pinfunction "1_1") (pintype "passive"))
      (node (ref "D3") (pin "2") (pinfunction "A_2") (pintype "bidirectional"))
      (node (ref "D4") (pin "1") (pinfunction "K_1") (pintype "bidirectional"))
    )
    (net (code "27") (name "Net-(D7-CATHODE)") (class "Default")
      (node (ref "D7") (pin "1") (pinfunction "CATHODE_1") (pintype "bidirectional"))
      (node (ref "R_CAPACITOR") (pin "2") (pinfunction "2_2") (pintype "passive"))
    )
    (net (code "28") (name "Net-(EPD_C1-Pad2)") (class "Default")
      (node (ref "EPD_C1") (pin "2") (pinfunction "2_2") (pintype "passive"))
      (node (ref "J1") (pin "4") (pinfunction "4_4") (pintype "bidirectional"))
    )
    (net (code "29") (name "Net-(EPD_C2-Pad2)") (class "Default")
      (node (ref "EPD_C2") (pin "2") (pinfunction "2_2") (pintype "passive"))
      (node (ref "J1") (pin "5") (pinfunction "5_5") (pintype "bidirectional"))
    )
    (net (code "30") (name "Net-(EPD_C6-Pad2)") (class "Default")
      (node (ref "EPD_C6") (pin "2") (pinfunction "2_2") (pintype "passive"))
      (node (ref "J1") (pin "18") (pinfunction "18_18") (pintype "bidirectional"))
    )
    (net (code "31") (name "Net-(EPD_C7-Pad2)") (class "Default")
      (node (ref "EPD_C7") (pin "2") (pinfunction "2_2") (pintype "passive"))
      (node (ref "J1") (pin "19") (pinfunction "19_19") (pintype "bidirectional"))
    )
    (net (code "32") (name "Net-(EPD_C8-Pad2)") (class "Default")
      (node (ref "EPD_C8") (pin "2") (pinfunction "2_2") (pintype "passive"))
      (node (ref "J1") (pin "20") (pinfunction "20_20") (pintype "bidirectional"))
    )
    (net (code "33") (name "Net-(EPD_C10-Pad2)") (class "Default")
      (node (ref "EPD_C10") (pin "2") (pinfunction "2_2") (pintype "passive"))
      (node (ref "J1") (pin "22") (pinfunction "22_22") (pintype "bidirectional"))
    )
    (net (code "34") (name "Net-(EPD_C12-Pad2)") (class "Default")
      (node (ref "EPD_C12") (pin "2") (pinfunction "2_2") (pintype "passive"))
      (node (ref "J1") (pin "24") (pinfunction "24_24") (pintype "bidirectional"))
    )
    (net (code "35") (name "Net-(IC1-CT)") (class "Default")
      (node (ref "C_DELAY") (pin "1") (pinfunction "1_1") (pintype "passive"))
      (node (ref "IC1") (pin "5") (pinfunction "CT_5") (pintype "bidirectional"))
    )
    (net (code "36") (name "Net-(J2-PadA5)") (class "Default")
      (node (ref "J2") (pin "A5") (pinfunction "A5_A5") (pintype "bidirectional"))
      (node (ref "R2-USB1") (pin "2") (pinfunction "2_2") (pintype "passive"))
    )
    (net (code "37") (name "Net-(J2-PadB5)") (class "Default")
      (node (ref "J2") (pin "B5") (pinfunction "B5_B5") (pintype "bidirectional"))
      (node (ref "R2-USB") (pin "1") (pinfunction "1_1") (pintype "passive"))
    )
    (net (code "38") (name "Net-(MCP73831-PROG)") (class "Default")
      (node (ref "MCP73831") (pin "5") (pinfunction "PROG_5") (pintype "input"))
      (node (ref "R2_BAT") (pin "2") (pinfunction "2_2") (pintype "passive"))
    )
    (net (code "39") (name "Net-(MCP73831-STAT)") (class "Default")
      (node (ref "MCP73831") (pin "1") (pinfunction "STAT_1") (pintype "output"))
      (node (ref "R1_BAT") (pin "1") (pinfunction "1_1") (pintype "passive"))
    )
    (net (code "40") (name "PREVGH") (class "Default")
      (node (ref "D5") (pin "1") (pinfunction "K_1") (pintype "bidirectional"))
      (node (ref "EPD_C9") (pin "2") (pinfunction "2_2") (pintype "passive"))
      (node (ref "J1") (pin "21") (pinfunction "21_21") (pintype "bidirectional"))
    )
    (net (code "41") (name "PREVGL") (class "Default")
      (node (ref "D4") (pin "2") (pinfunction "A_2") (pintype "bidirectional"))
      (node (ref "EPD_C11") (pin "2") (pinfunction "2_2") (pintype "passive"))
      (node (ref "J1") (pin "23") (pinfunction "23_23") (pintype "bidirectional"))
    )
    (net (code "42") (name "RESE") (class "Default")
      (node (ref "J1") (pin "3") (pinfunction "3_3") (pintype "bidirectional"))
      (node (ref "Q3") (pin "2") (pinfunction "S_2") (pintype "bidirectional"))
      (node (ref "R3") (pin "1") (pinfunction "1_1") (pintype "passive"))
    )
    (net (code "43") (name "RESE'") (class "Default")
      (node (ref "R2") (pin "2") (pinfunction "2_2") (pintype "passive"))
      (node (ref "R3") (pin "2") (pinfunction "2_2") (pintype "passive"))
      (node (ref "SJ1") (pin "2") (pinfunction "2_2") (pintype "passive"))
    )
    (net (code "44") (name "RESET") (class "Default")
      (node (ref "C5") (pin "1") (pinfunction "1_1") (pintype "passive"))
      (node (ref "IC1") (pin "1") (pinfunction "VOUT_1") (pintype "bidirectional"))
      (node (ref "RESET_BUTTON") (pin "3") (pinfunction "3_3") (pintype "passive"))
      (node (ref "RESET_BUTTON") (pin "4") (pinfunction "4_4") (pintype "passive"))
      (node (ref "R_RESET") (pin "1") (pinfunction "1_1") (pintype "passive"))
      (node (ref "U2") (pin "3") (pinfunction "EN_3") (pintype "input"))
    )
    (net (code "45") (name "RTC_RST") (class "Default")
      (node (ref "U2") (pin "16") (pinfunction "IO18_16") (pintype "bidirectional"))
      (node (ref "U3") (pin "4") (pinfunction "~{RST}_4") (pintype "input"))
    )
    (net (code "46") (name "RX") (class "Default")
      (node (ref "TP2") (pin "TP") (pinfunction "TP_TP") (pintype "input"))
      (node (ref "U2") (pin "24") (pinfunction "RXD0/GPIO17_24") (pintype "bidirectional"))
    )
    (net (code "47") (name "SCK") (class "Default")
      (node (ref "D10") (pin "1") (pinfunction "1_1") (pintype "passive"))
      (node (ref "J1") (pin "13") (pinfunction "13_13") (pintype "bidirectional"))
      (node (ref "J4") (pin "P5") (pinfunction "CLK_P5") (pintype "bidirectional"))
      (node (ref "R6") (pin "1") (pinfunction "1_1") (pintype "passive"))
      (node (ref "TP8") (pin "TP") (pinfunction "TP_TP") (pintype "input"))
      (node (ref "U1") (pin "6") (pinfunction "CLK_6") (pintype "input"))
      (node (ref "U2") (pin "6") (pinfunction "IO6_6") (pintype "bidirectional"))
    )
    (net (code "48") (name "SCL") (class "Default")
      (node (ref "J3") (pin "4") (pinfunction "4_4") (pintype "passive"))
      (node (ref "R2-PINH") (pin "1") (pinfunction "1_1") (pintype "passive"))
      (node (ref "SENSOR2") (pin "4") (pinfunction "SCK_4") (pintype "input"))
      (node (ref "U2") (pin "20") (pinfunction "IO22_20") (pintype "bidirectional"))
      (node (ref "U3") (pin "16") (pinfunction "SCL_16") (pintype "input"))
      (node (ref "U4") (pin "7") (pinfunction "SCL_7") (pintype "input"))
    )
    (net (code "49") (name "SDA") (class "Default")
      (node (ref "J3") (pin "3") (pinfunction "3_3") (pintype "passive"))
      (node (ref "R1_PINH") (pin "1") (pinfunction "1_1") (pintype "passive"))
      (node (ref "SENSOR2") (pin "3") (pinfunction "SDI_3") (pintype "bidirectional"))
      (node (ref "U2") (pin "19") (pinfunction "IO21_19") (pintype "bidirectional"))
      (node (ref "U3") (pin "15") (pinfunction "SDA_15") (pintype "bidirectional"))
      (node (ref "U4") (pin "8") (pinfunction "SDA_8") (pintype "bidirectional"))
    )
    (net (code "50") (name "SRC") (class "Default")
      (node (ref "C4") (pin "2") (pinfunction "2_2") (pintype "passive"))
      (node (ref "D5") (pin "2") (pinfunction "A_2") (pintype "bidirectional"))
      (node (ref "L1") (pin "1") (pinfunction "1_1") (pintype "passive"))
      (node (ref "Q3") (pin "3") (pinfunction "D_3") (pintype "bidirectional"))
    )
    (net (code "51") (name "SS_SD") (class "Default")
      (node (ref "D6") (pin "1") (pinfunction "1_1") (pintype "passive"))
      (node (ref "J4") (pin "P2") (pinfunction "CD/DAT3_P2") (pintype "bidirectional"))
      (node (ref "R10") (pin "1") (pinfunction "1_1") (pintype "passive"))
      (node (ref "U2") (pin "4") (pinfunction "IO4_4") (pintype "bidirectional"))
    )
    (net (code "52") (name "TX") (class "Default")
      (node (ref "TP1") (pin "TP") (pinfunction "TP_TP") (pintype "input"))
      (node (ref "U2") (pin "25") (pinfunction "TXD0/GPIO16_25") (pintype "bidirectional"))
    )
    (net (code "53") (name "USB_D+") (class "Default")
      (node (ref "D1") (pin "3") (pinfunction "I/O2_1_3") (pintype "bidirectional"))
      (node (ref "U2") (pin "14") (pinfunction "IO13_14") (pintype "bidirectional"))
    )
    (net (code "54") (name "USB_D-") (class "Default")
      (node (ref "D1") (pin "1") (pinfunction "I/O1_1_1") (pintype "bidirectional"))
      (node (ref "U2") (pin "13") (pinfunction "IO12_13") (pintype "bidirectional"))
    )
    (net (code "55") (name "VBAT") (class "Default")
      (node (ref "C2_BAT") (pin "1") (pinfunction "1_1") (pintype "passive"))
      (node (ref "MCP73831") (pin "3") (pinfunction "VBAT_3") (pintype "power_in"))
      (node (ref "Q1") (pin "3") (pinfunction "D_3") (pintype "bidirectional"))
      (node (ref "TP3") (pin "TP") (pinfunction "TP_TP") (pintype "input"))
      (node (ref "U4") (pin "2") (pinfunction "CELL_2") (pintype "power_in"))
      (node (ref "U4") (pin "3") (pinfunction "VDD_3") (pintype "power_in"))
    )
    (net (code "56") (name "VBUS") (class "Default")
      (node (ref "C1_BAT") (pin "1") (pinfunction "1_1") (pintype "passive"))
      (node (ref "C4_USB") (pin "1") (pinfunction "1_1") (pintype "passive"))
      (node (ref "C5_USB") (pin "1") (pinfunction "1_1") (pintype "passive"))
      (node (ref "CHG_LED") (pin "A") (pinfunction "A_A") (pintype "passive"))
      (node (ref "D1") (pin "5") (pinfunction "VBUS_5") (pintype "bidirectional"))
      (node (ref "D2") (pin "2") (pinfunction "ANODE_2") (pintype "bidirectional"))
      (node (ref "MCP73831") (pin "4") (pinfunction "VIN_4") (pintype "power_in"))
      (node (ref "PFMF.050.1") (pin "2") (pinfunction "2_2") (pintype "passive"))
      (node (ref "Q1") (pin "1") (pinfunction "G_1") (pintype "bidirectional"))
      (node (ref "R1_PWRUSB") (pin "2") (pinfunction "2_2") (pintype "passive"))
      (node (ref "TP14") (pin "TP") (pinfunction "TP_TP") (pintype "input"))
    )
    (net (code "57") (name "VRTC") (class "Default")
      (node (ref "C10_SUPERCAP") (pin "2") (pinfunction "2_2") (pintype "passive"))
      (node (ref "C8") (pin "1") (pinfunction "1_1") (pintype "passive"))
      (node (ref "R_CAPACITOR") (pin "1") (pinfunction "1_1") (pintype "passive"))
      (node (ref "U3") (pin "14") (pinfunction "VBAT_14") (pintype "power_in"))
    )
    (net (code "58") (name "VUSB") (class "Default")
      (node (ref "J2") (pin "A4") (pinfunction "A4_A4") (pintype "bidirectional"))
      (node (ref "J2") (pin "A9") (pinfunction "A9_A9") (pintype "bidirectional"))
      (node (ref "J2") (pin "B4") (pinfunction "B4_B4") (pintype "bidirectional"))
      (node (ref "J2") (pin "B9") (pinfunction "B9_B9") (pintype "bidirectional"))
      (node (ref "PFMF.050.1") (pin "1") (pinfunction "1_1") (pintype "passive"))
    )
    (net (code "59") (name "unconnected-(IC1-NC-Pad4)") (class "Default")
      (node (ref "IC1") (pin "4") (pinfunction "NC_4") (pintype "no_connect"))
    )
    (net (code "60") (name "unconnected-(IC1-VDD-Pad2)") (class "Default")
      (node (ref "IC1") (pin "2") (pinfunction "VDD_2") (pintype "bidirectional"))
    )
    (net (code "61") (name "unconnected-(IC4-NC-Pad4)") (class "Default")
      (node (ref "IC4") (pin "4") (pinfunction "NC_4") (pintype "no_connect"))
    )
    (net (code "62") (name "unconnected-(J1-Pad1)") (class "Default")
      (node (ref "J1") (pin "1") (pinfunction "1_1") (pintype "bidirectional"))
    )
    (net (code "63") (name "unconnected-(J1-Pad6)") (class "Default")
      (node (ref "J1") (pin "6") (pinfunction "6_6") (pintype "bidirectional"))
    )
    (net (code "64") (name "unconnected-(J1-Pad7)") (class "Default")
      (node (ref "J1") (pin "7") (pinfunction "7_7") (pintype "bidirectional"))
    )
    (net (code "65") (name "unconnected-(J2-PadA8)") (class "Default")
      (node (ref "J2") (pin "A8") (pinfunction "A8_A8") (pintype "bidirectional"))
    )
    (net (code "66") (name "unconnected-(J2-PadB8)") (class "Default")
      (node (ref "J2") (pin "B8") (pinfunction "B8_B8") (pintype "bidirectional"))
    )
    (net (code "67") (name "unconnected-(J4-DAT1-PadP8)") (class "Default")
      (node (ref "J4") (pin "P8") (pinfunction "DAT1_P8") (pintype "bidirectional"))
    )
    (net (code "68") (name "unconnected-(J4-DAT2-PadP1)") (class "Default")
      (node (ref "J4") (pin "P1") (pinfunction "DAT2_P1") (pintype "bidirectional"))
    )
    (net (code "69") (name "unconnected-(J4-DETECTION_1-PadS1)") (class "Default")
      (node (ref "J4") (pin "S1") (pinfunction "DETECTION_1_S1") (pintype "bidirectional"))
    )
    (net (code "70") (name "unconnected-(J4-DETECTION_2-PadS2)") (class "Default")
      (node (ref "J4") (pin "S2") (pinfunction "DETECTION_2_S2") (pintype "bidirectional"))
    )
    (net (code "71") (name "unconnected-(U2-NC-Pad22)") (class "Default")
      (node (ref "U2") (pin "22") (pinfunction "NC_22") (pintype "no_connect"))
    )
    (net (code "72") (name "unconnected-(U4-~{ALERT}-Pad5)") (class "Default")
      (node (ref "U4") (pin "5") (pinfunction "~{ALERT}_5") (pintype "output"))
    )
  )
)
